# mcu.net
KiCad netlist of a schematic drawn in Altium Designer
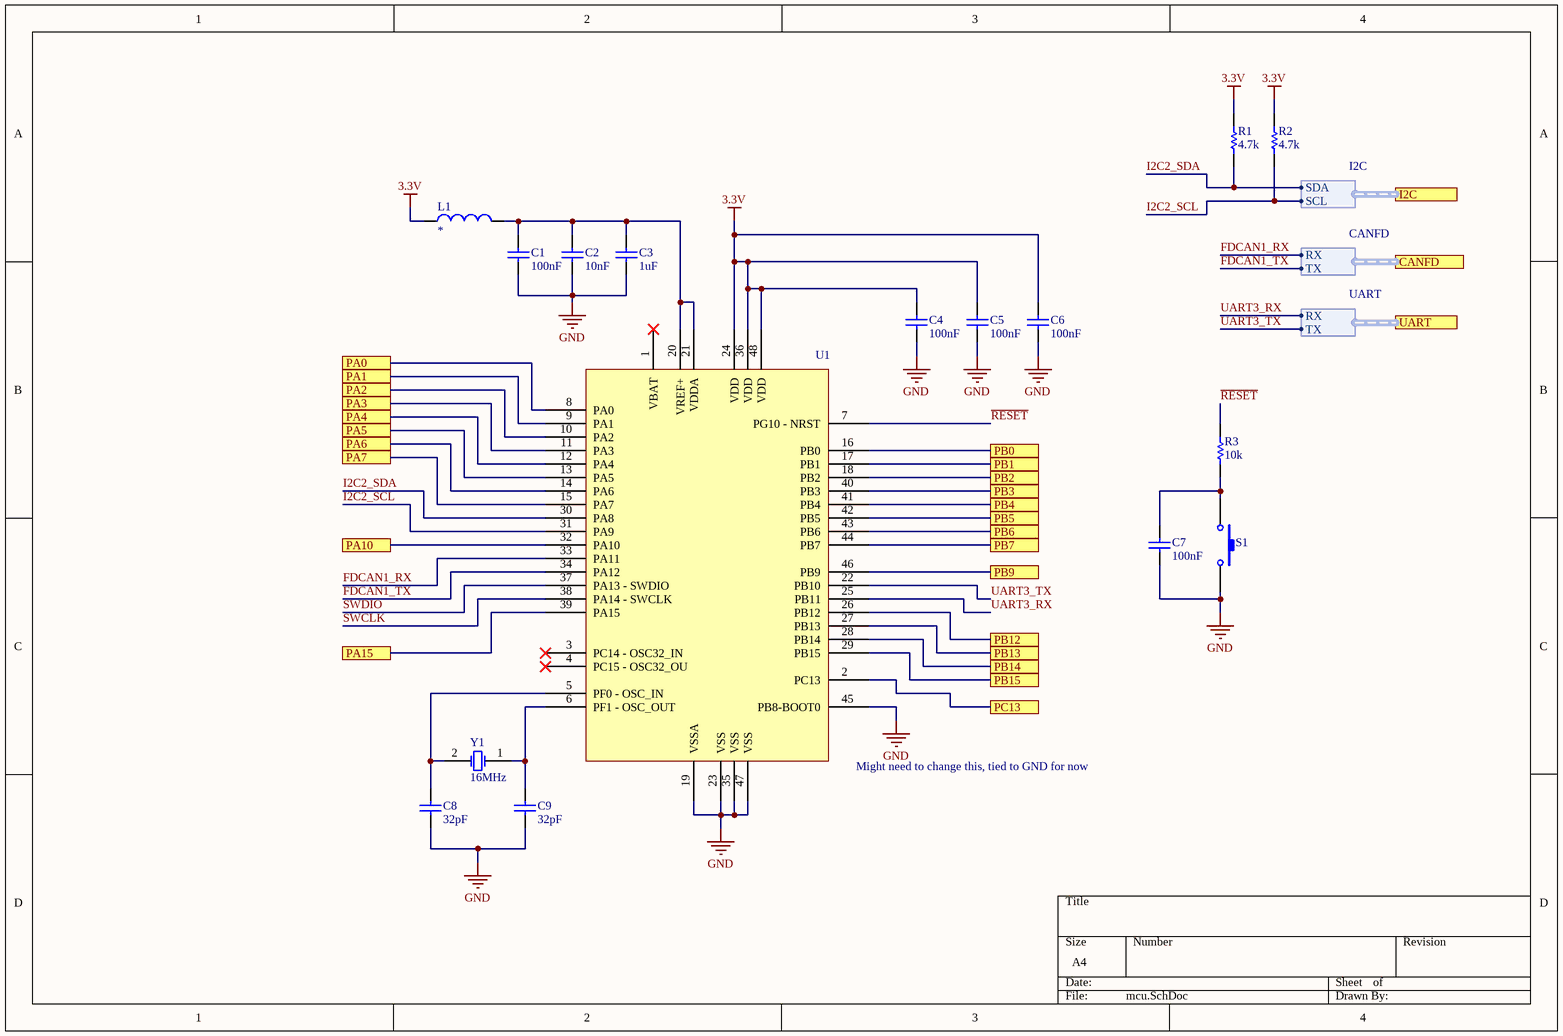
[diagram p0: mcu.SchDoc]

(export (version "E")
  (design (tool "Eeschema 10.0.6"))
  (components
    (comp (ref "C1")
      (value "100nF")
      (footprint "0603 - Capacitor")
      (description "Nonpolarized Capacitor")
      (fields (field (name "Comment") "Capacitor - Nonpolarized"))
      (libsource (lib "General") (part "Capacitor - Nonpolarized"))
    )
    (comp (ref "C2")
      (value "10nF")
      (footprint "0603 - Capacitor")
      (description "Nonpolarized Capacitor")
      (fields (field (name "Comment") "Capacitor - Nonpolarized"))
      (libsource (lib "General") (part "Capacitor - Nonpolarized"))
    )
    (comp (ref "C3")
      (value "1uF")
      (footprint "0603 - Capacitor")
      (description "Nonpolarized Capacitor")
      (fields (field (name "Comment") "Capacitor - Nonpolarized"))
      (libsource (lib "General") (part "Capacitor - Nonpolarized"))
    )
    (comp (ref "C4")
      (value "100nF")
      (footprint "0603 - Capacitor")
      (description "Nonpolarized Capacitor")
      (fields (field (name "Comment") "Capacitor - Nonpolarized"))
      (libsource (lib "General") (part "Capacitor - Nonpolarized"))
    )
    (comp (ref "C5")
      (value "100nF")
      (footprint "0603 - Capacitor")
      (description "Nonpolarized Capacitor")
      (fields (field (name "Comment") "Capacitor - Nonpolarized"))
      (libsource (lib "General") (part "Capacitor - Nonpolarized"))
    )
    (comp (ref "C6")
      (value "100nF")
      (footprint "0603 - Capacitor")
      (description "Nonpolarized Capacitor")
      (fields (field (name "Comment") "Capacitor - Nonpolarized"))
      (libsource (lib "General") (part "Capacitor - Nonpolarized"))
    )
    (comp (ref "C7")
      (value "100nF")
      (footprint "0603 - Capacitor")
      (description "Nonpolarized Capacitor")
      (fields (field (name "Comment") "Capacitor - Nonpolarized"))
      (libsource (lib "General") (part "Capacitor - Nonpolarized"))
    )
    (comp (ref "C8")
      (value "32pF")
      (footprint "0603 - Capacitor")
      (description "Nonpolarized Capacitor")
      (fields (field (name "Comment") "Capacitor - Nonpolarized"))
      (libsource (lib "General") (part "Capacitor - Nonpolarized"))
    )
    (comp (ref "C9")
      (value "32pF")
      (footprint "0603 - Capacitor")
      (description "Nonpolarized Capacitor")
      (fields (field (name "Comment") "Capacitor - Nonpolarized"))
      (libsource (lib "General") (part "Capacitor - Nonpolarized"))
    )
    (comp (ref "L1")
      (value "Inductor")
      (footprint "MSS1210 - INDUCTOR")
      (fields (field (name "ALTIUM_VALUE") "*"))
      (libsource (lib "General") (part "Inductor"))
    )
    (comp (ref "R1")
      (value "4.7k")
      (footprint "0603 - Resistor")
      (description "Resistor")
      (libsource (lib "General") (part "Resistor"))
    )
    (comp (ref "R2")
      (value "4.7k")
      (footprint "0603 - Resistor")
      (description "Resistor")
      (libsource (lib "General") (part "Resistor"))
    )
    (comp (ref "R3")
      (value "10k")
      (footprint "0603 - Resistor")
      (description "Resistor")
      (libsource (lib "General") (part "Resistor"))
    )
    (comp (ref "S1")
      (value "Switch - Push Button")
      (footprint "6x6mm Switch")
      (description "Push Button Switch")
      (libsource (lib "General") (part "Switch - Push Button"))
    )
    (comp (ref "U1")
      (value "STM32G431C6T6")
      (footprint "TSQFP50P900X900X160-48N")
      (description "MCU 32BIT 32KB FLASH 48LQFP")
      (fields (field (name "MANUFACTURER") "ST"))
      (libsource (lib "GeneralComponents") (part "STM32G431C6T6"))
    )
    (comp (ref "Y1")
      (value "16MHz")
      (footprint "2-SMD NO LEAD CRSYSTAL")
      (description "Crystal Oscillator")
      (fields (field (name "Comment") "Oscillator"))
      (libsource (lib "General") (part "Oscillator"))
    )
  )
  (nets
    (net (code "4") (name "/FDCAN1_RX") (class "Default")
      (node (ref "U1") (pin "33") (pinfunction "PA11_33") (pintype "passive"))
    )
    (net (code "5") (name "/FDCAN1_TX") (class "Default")
      (node (ref "U1") (pin "34") (pinfunction "PA12_34") (pintype "passive"))
    )
    (net (code "6") (name "/I2C2_SCL") (class "Default")
      (node (ref "R2") (pin "1") (pinfunction "1_1") (pintype "passive"))
      (node (ref "U1") (pin "31") (pinfunction "PA9_31") (pintype "passive"))
    )
    (net (code "7") (name "/I2C2_SDA") (class "Default")
      (node (ref "R1") (pin "1") (pinfunction "1_1") (pintype "passive"))
      (node (ref "U1") (pin "30") (pinfunction "PA8_30") (pintype "passive"))
    )
    (net (code "8") (name "/PA0") (class "Default")
      (node (ref "U1") (pin "8") (pinfunction "PA0_8") (pintype "passive"))
    )
    (net (code "9") (name "/PA1") (class "Default")
      (node (ref "U1") (pin "9") (pinfunction "PA1_9") (pintype "passive"))
    )
    (net (code "10") (name "/PA2") (class "Default")
      (node (ref "U1") (pin "10") (pinfunction "PA2_10") (pintype "passive"))
    )
    (net (code "11") (name "/PA3") (class "Default")
      (node (ref "U1") (pin "11") (pinfunction "PA3_11") (pintype "passive"))
    )
    (net (code "12") (name "/PA4") (class "Default")
      (node (ref "U1") (pin "12") (pinfunction "PA4_12") (pintype "passive"))
    )
    (net (code "13") (name "/PA5") (class "Default")
      (node (ref "U1") (pin "13") (pinfunction "PA5_13") (pintype "passive"))
    )
    (net (code "14") (name "/PA6") (class "Default")
      (node (ref "U1") (pin "14") (pinfunction "PA6_14") (pintype "passive"))
    )
    (net (code "15") (name "/PA7") (class "Default")
      (node (ref "U1") (pin "15") (pinfunction "PA7_15") (pintype "passive"))
    )
    (net (code "16") (name "/PA10") (class "Default")
      (node (ref "U1") (pin "32") (pinfunction "PA10_32") (pintype "passive"))
    )
    (net (code "17") (name "/PA15") (class "Default")
      (node (ref "U1") (pin "39") (pinfunction "PA15_39") (pintype "passive"))
    )
    (net (code "18") (name "/PB0") (class "Default")
      (node (ref "U1") (pin "16") (pinfunction "PB0_16") (pintype "passive"))
    )
    (net (code "19") (name "/PB1") (class "Default")
      (node (ref "U1") (pin "17") (pinfunction "PB1_17") (pintype "passive"))
    )
    (net (code "20") (name "/PB2") (class "Default")
      (node (ref "U1") (pin "18") (pinfunction "PB2_18") (pintype "passive"))
    )
    (net (code "21") (name "/PB3") (class "Default")
      (node (ref "U1") (pin "40") (pinfunction "PB3_40") (pintype "passive"))
    )
    (net (code "22") (name "/PB4") (class "Default")
      (node (ref "U1") (pin "41") (pinfunction "PB4_41") (pintype "passive"))
    )
    (net (code "23") (name "/PB5") (class "Default")
      (node (ref "U1") (pin "42") (pinfunction "PB5_42") (pintype "passive"))
    )
    (net (code "24") (name "/PB6") (class "Default")
      (node (ref "U1") (pin "43") (pinfunction "PB6_43") (pintype "passive"))
    )
    (net (code "25") (name "/PB7") (class "Default")
      (node (ref "U1") (pin "44") (pinfunction "PB7_44") (pintype "passive"))
    )
    (net (code "26") (name "/PB9") (class "Default")
      (node (ref "U1") (pin "46") (pinfunction "PB9_46") (pintype "passive"))
    )
    (net (code "27") (name "/PB12") (class "Default")
      (node (ref "U1") (pin "26") (pinfunction "PB12_26") (pintype "passive"))
    )
    (net (code "28") (name "/PB13") (class "Default")
      (node (ref "U1") (pin "27") (pinfunction "PB13_27") (pintype "passive"))
    )
    (net (code "29") (name "/PB14") (class "Default")
      (node (ref "U1") (pin "28") (pinfunction "PB14_28") (pintype "passive"))
    )
    (net (code "30") (name "/PB15") (class "Default")
      (node (ref "U1") (pin "29") (pinfunction "PB15_29") (pintype "passive"))
    )
    (net (code "31") (name "/PC13") (class "Default")
      (node (ref "U1") (pin "2") (pinfunction "PC13_2") (pintype "passive"))
    )
    (net (code "32") (name "/SWCLK") (class "Default")
      (node (ref "U1") (pin "38") (pinfunction "PA14_-_SWCLK_38") (pintype "passive"))
    )
    (net (code "33") (name "/SWDIO") (class "Default")
      (node (ref "U1") (pin "37") (pinfunction "PA13_-_SWDIO_37") (pintype "passive"))
    )
    (net (code "34") (name "/UART3_RX") (class "Default")
      (node (ref "U1") (pin "25") (pinfunction "PB11_25") (pintype "passive"))
    )
    (net (code "35") (name "/UART3_TX") (class "Default")
      (node (ref "U1") (pin "22") (pinfunction "PB10_22") (pintype "passive"))
    )
    (net (code "39") (name "/~{RESET}") (class "Default")
      (node (ref "R3") (pin "2") (pinfunction "2_2") (pintype "passive"))
      (node (ref "U1") (pin "7") (pinfunction "PG10_-_NRST_7") (pintype "passive"))
    )
    (net (code "40") (name "3.3V") (class "Default")
      (node (ref "C4") (pin "2") (pinfunction "2_2") (pintype "passive"))
      (node (ref "C5") (pin "2") (pinfunction "2_2") (pintype "passive"))
      (node (ref "C6") (pin "2") (pinfunction "2_2") (pintype "passive"))
      (node (ref "L1") (pin "1") (pinfunction "1_1") (pintype "passive"))
      (node (ref "R1") (pin "2") (pinfunction "2_2") (pintype "passive"))
      (node (ref "R2") (pin "2") (pinfunction "2_2") (pintype "passive"))
      (node (ref "U1") (pin "24") (pinfunction "VDD_24") (pintype "power_in"))
      (node (ref "U1") (pin "36") (pinfunction "VDD_36") (pintype "power_in"))
      (node (ref "U1") (pin "48") (pinfunction "VDD_48") (pintype "power_in"))
    )
    (net (code "41") (name "GND") (class "Default")
      (node (ref "C1") (pin "1") (pinfunction "1_1") (pintype "passive"))
      (node (ref "C2") (pin "1") (pinfunction "1_1") (pintype "passive"))
      (node (ref "C3") (pin "1") (pinfunction "1_1") (pintype "passive"))
      (node (ref "C4") (pin "1") (pinfunction "1_1") (pintype "passive"))
      (node (ref "C5") (pin "1") (pinfunction "1_1") (pintype "passive"))
      (node (ref "C6") (pin "1") (pinfunction "1_1") (pintype "passive"))
      (node (ref "C7") (pin "1") (pinfunction "1_1") (pintype "passive"))
      (node (ref "C8") (pin "1") (pinfunction "1_1") (pintype "passive"))
      (node (ref "C9") (pin "1") (pinfunction "1_1") (pintype "passive"))
      (node (ref "S1") (pin "2") (pinfunction "2_2") (pintype "passive"))
      (node (ref "U1") (pin "19") (pinfunction "VSSA_19") (pintype "power_in"))
      (node (ref "U1") (pin "23") (pinfunction "VSS_23") (pintype "power_in"))
      (node (ref "U1") (pin "35") (pinfunction "VSS_35") (pintype "power_in"))
      (node (ref "U1") (pin "45") (pinfunction "PB8-BOOT0_45") (pintype "passive"))
      (node (ref "U1") (pin "47") (pinfunction "VSS_47") (pintype "power_in"))
    )
    (net (code "42") (name "Net-(C7-Pad2)") (class "Default")
      (node (ref "C7") (pin "2") (pinfunction "2_2") (pintype "passive"))
      (node (ref "R3") (pin "1") (pinfunction "1_1") (pintype "passive"))
      (node (ref "S1") (pin "1") (pinfunction "1_1") (pintype "passive"))
    )
    (net (code "43") (name "Net-(U1-PF0_-_OSC_IN)") (class "Default")
      (node (ref "C8") (pin "2") (pinfunction "2_2") (pintype "passive"))
      (node (ref "U1") (pin "5") (pinfunction "PF0_-_OSC_IN_5") (pintype "passive"))
      (node (ref "Y1") (pin "2") (pinfunction "OSC2_2") (pintype "passive"))
    )
    (net (code "44") (name "Net-(U1-PF1_-_OSC_OUT)") (class "Default")
      (node (ref "C9") (pin "2") (pinfunction "2_2") (pintype "passive"))
      (node (ref "U1") (pin "6") (pinfunction "PF1_-_OSC_OUT_6") (pintype "passive"))
      (node (ref "Y1") (pin "1") (pinfunction "OSC1_1") (pintype "passive"))
    )
    (net (code "45") (name "Net-(U1-VDDA)") (class "Default")
      (node (ref "C1") (pin "2") (pinfunction "2_2") (pintype "passive"))
      (node (ref "C2") (pin "2") (pinfunction "2_2") (pintype "passive"))
      (node (ref "C3") (pin "2") (pinfunction "2_2") (pintype "passive"))
      (node (ref "L1") (pin "2") (pinfunction "2_2") (pintype "passive"))
      (node (ref "U1") (pin "20") (pinfunction "VREF+_20") (pintype "power_in"))
      (node (ref "U1") (pin "21") (pinfunction "VDDA_21") (pintype "power_in"))
    )
    (net (code "46") (name "unconnected-(U1-PC14_-_OSC32_IN-Pad3)") (class "Default")
      (node (ref "U1") (pin "3") (pinfunction "PC14_-_OSC32_IN_3") (pintype "passive+no_connect"))
    )
    (net (code "47") (name "unconnected-(U1-PC15_-_OSC32_OU-Pad4)") (class "Default")
      (node (ref "U1") (pin "4") (pinfunction "PC15_-_OSC32_OU_4") (pintype "passive+no_connect"))
    )
    (net (code "48") (name "unconnected-(U1-VBAT-Pad1)") (class "Default")
      (node (ref "U1") (pin "1") (pinfunction "VBAT_1") (pintype "power_in+no_connect"))
    )
  )
)
